# Remote_Control.net
KiCad netlist of a schematic drawn in Altium Designer
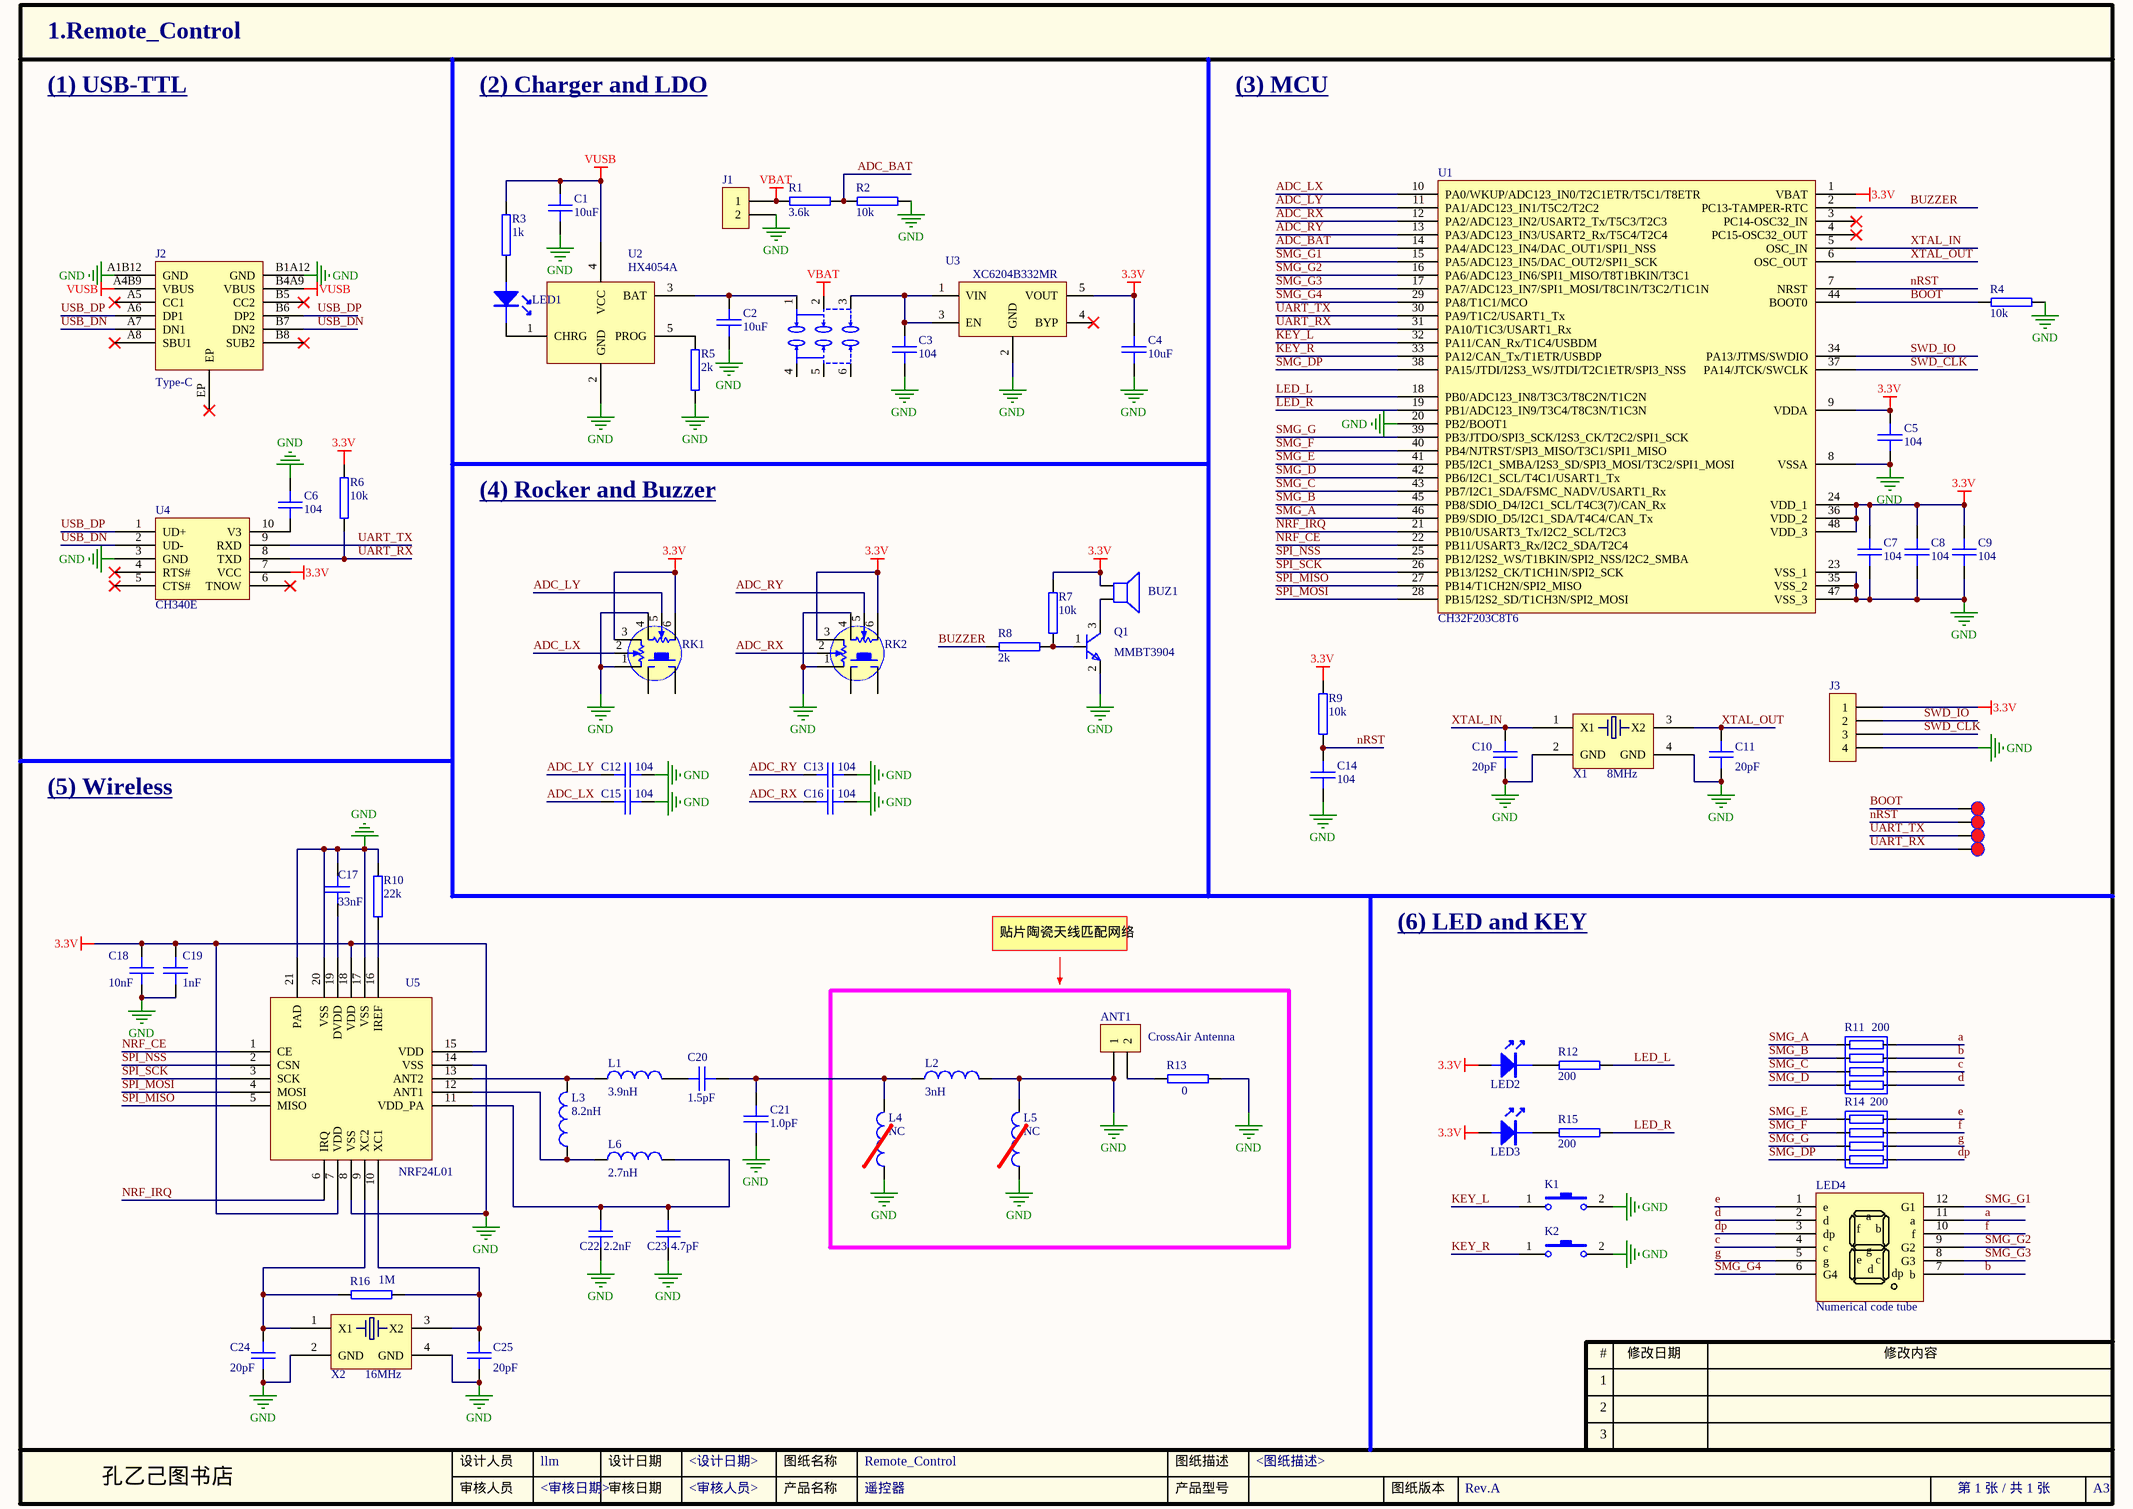
[diagram p0: Remote_Control.SchDoc]

(export (version "E")
  (design (tool "Eeschema 10.0.6"))
  (components
    (comp (ref "ANT1")
      (value "CrossAir Antenna")
      (footprint "ANT-SMD_L3.1-W1.6")
      (description "Connector")
      (libsource (lib "") (part "CON2_1"))
    )
    (comp (ref "BOOT")
      (value "BOOT")
      (footprint "PAD-40")
      (description "测试点")
      (libsource (lib "MY_Schlib") (part "TEST-DOT"))
    )
    (comp (ref "BUZ1")
      (value "BUZZER")
      (footprint "BUZ-TH_BD9.6-P5.00-D0.7-FD")
      (description "蜂鸣器")
      (libsource (lib "Schlib1") (part "BUZZER"))
    )
    (comp (ref "C1")
      (value "10uF")
      (footprint "0805C")
      (description "电容")
      (libsource (lib "MY_Schlib") (part "CAP"))
    )
    (comp (ref "C2")
      (value "10uF")
      (footprint "0805C")
      (description "电容")
      (libsource (lib "MY_Schlib") (part "CAP"))
    )
    (comp (ref "C3")
      (value "104")
      (footprint "0402C")
      (description "电容")
      (libsource (lib "MY_Schlib") (part "CAP"))
    )
    (comp (ref "C4")
      (value "10uF")
      (footprint "0805C")
      (description "电容")
      (libsource (lib "MY_Schlib") (part "CAP"))
    )
    (comp (ref "C5")
      (value "104")
      (footprint "0402C")
      (description "电容")
      (libsource (lib "MY_Schlib") (part "CAP"))
    )
    (comp (ref "C6")
      (value "104")
      (footprint "0402C")
      (description "电容")
      (libsource (lib "MY_Schlib") (part "CAP"))
    )
    (comp (ref "C7")
      (value "104")
      (footprint "0402C")
      (description "电容")
      (libsource (lib "MY_Schlib") (part "CAP"))
    )
    (comp (ref "C8")
      (value "104")
      (footprint "0402C")
      (description "电容")
      (libsource (lib "MY_Schlib") (part "CAP"))
    )
    (comp (ref "C9")
      (value "104")
      (footprint "0402C")
      (description "电容")
      (libsource (lib "MY_Schlib") (part "CAP"))
    )
    (comp (ref "C10")
      (value "20pF")
      (footprint "0402C")
      (description "电容")
      (libsource (lib "MY_Schlib") (part "CAP"))
    )
    (comp (ref "C11")
      (value "20pF")
      (footprint "0402C")
      (description "电容")
      (libsource (lib "MY_Schlib") (part "CAP"))
    )
    (comp (ref "C12")
      (value "104")
      (footprint "0402C")
      (description "电容")
      (libsource (lib "MY_Schlib") (part "CAP"))
    )
    (comp (ref "C13")
      (value "104")
      (footprint "0402C")
      (description "电容")
      (libsource (lib "MY_Schlib") (part "CAP"))
    )
    (comp (ref "C14")
      (value "104")
      (footprint "0402C")
      (description "电容")
      (libsource (lib "MY_Schlib") (part "CAP"))
    )
    (comp (ref "C15")
      (value "104")
      (footprint "0402C")
      (description "电容")
      (libsource (lib "MY_Schlib") (part "CAP"))
    )
    (comp (ref "C16")
      (value "104")
      (footprint "0402C")
      (description "电容")
      (libsource (lib "MY_Schlib") (part "CAP"))
    )
    (comp (ref "C17")
      (value "33nF")
      (footprint "0402C")
      (description "电容")
      (libsource (lib "MY_Schlib") (part "CAP"))
    )
    (comp (ref "C18")
      (value "10nF")
      (footprint "0402C")
      (description "电容")
      (libsource (lib "MY_Schlib") (part "CAP"))
    )
    (comp (ref "C19")
      (value "1nF")
      (footprint "0402C")
      (description "电容")
      (libsource (lib "MY_Schlib") (part "CAP"))
    )
    (comp (ref "C20")
      (value "1.5pF")
      (footprint "0402C")
      (description "电容")
      (libsource (lib "MY_Schlib") (part "CAP"))
    )
    (comp (ref "C21")
      (value "1.0pF")
      (footprint "0402C")
      (description "电容")
      (libsource (lib "MY_Schlib") (part "CAP"))
    )
    (comp (ref "C22")
      (value "2.2nF")
      (footprint "0402C")
      (description "电容")
      (libsource (lib "MY_Schlib") (part "CAP"))
    )
    (comp (ref "C23")
      (value "4.7pF")
      (footprint "0402C")
      (description "电容")
      (libsource (lib "MY_Schlib") (part "CAP"))
    )
    (comp (ref "C24")
      (value "20pF")
      (footprint "0402C")
      (description "电容")
      (libsource (lib "MY_Schlib") (part "CAP"))
    )
    (comp (ref "C25")
      (value "20pF")
      (footprint "0402C")
      (description "电容")
      (libsource (lib "MY_Schlib") (part "CAP"))
    )
    (comp (ref "J1")
      (value "CON2")
      (footprint "SIP-2-2.54")
      (description "Connector")
      (libsource (lib "MY_Schlib") (part "CON2"))
    )
    (comp (ref "J2")
      (value "Type-C")
      (footprint "USB-C-SMD_TYPE-C-16P-1")
      (libsource (lib "MY_Schlib") (part "Type-C"))
    )
    (comp (ref "J3")
      (value "CON4")
      (footprint "SIP-4-2.54")
      (description "Connector")
      (libsource (lib "MY_Schlib") (part "CON4"))
    )
    (comp (ref "K1")
      (value "BUTTON")
      (footprint "KEY-TH_4P-L7.5-W6.8-P4.50-LS7.2")
      (description "按键开关")
      (libsource (lib "MY_Schlib") (part "BUTTON"))
    )
    (comp (ref "K2")
      (value "BUTTON")
      (footprint "KEY-TH_4P-L7.5-W6.8-P4.50-LS7.2")
      (description "按键开关")
      (libsource (lib "MY_Schlib") (part "BUTTON"))
    )
    (comp (ref "L1")
      (value "3.9nH")
      (footprint "0402R")
      (description "电感")
      (libsource (lib "MY_Schlib") (part "INDUCTOR_1"))
    )
    (comp (ref "L2")
      (value "3nH")
      (footprint "0402R")
      (description "电感")
      (libsource (lib "MY_Schlib") (part "INDUCTOR_1"))
    )
    (comp (ref "L3")
      (value "8.2nH")
      (footprint "0402R")
      (description "电感")
      (libsource (lib "") (part "INDUCTOR_1_1"))
    )
    (comp (ref "L4")
      (value "NC")
      (footprint "0402R")
      (description "电感")
      (libsource (lib "") (part "INDUCTOR_1_1"))
    )
    (comp (ref "L5")
      (value "NC")
      (footprint "0402R")
      (description "电感")
      (libsource (lib "") (part "INDUCTOR_1_1"))
    )
    (comp (ref "L6")
      (value "2.7nH")
      (footprint "0402R")
      (description "电感")
      (libsource (lib "MY_Schlib") (part "INDUCTOR_1"))
    )
    (comp (ref "LED1")
      (value "Red")
      (footprint "LED-0603")
      (description "发光二极管")
      (libsource (lib "MY_Schlib") (part "LED"))
    )
    (comp (ref "LED2")
      (value "Blue")
      (footprint "LED-0603")
      (description "发光二极管")
      (libsource (lib "MY_Schlib") (part "LED"))
    )
    (comp (ref "LED3")
      (value "Blue")
      (footprint "LED-0603")
      (description "发光二极管")
      (libsource (lib "MY_Schlib") (part "LED"))
    )
    (comp (ref "LED4")
      (value "Numerical code tube")
      (footprint "0.28寸四位共阴数码管")
      (description "四位共阴数码管")
      (libsource (lib "Schlib1") (part "Numerical code tube"))
    )
    (comp (ref "Q1")
      (value "MMBT3904")
      (footprint "SOT-23")
      (description "NPN三极管")
      (libsource (lib "MY_Schlib") (part "NPN"))
    )
    (comp (ref "R1")
      (value "3.6k")
      (footprint "0402R")
      (description "电阻")
      (libsource (lib "MY_Schlib") (part "RES"))
    )
    (comp (ref "R2")
      (value "10k")
      (footprint "0402R")
      (description "电阻")
      (libsource (lib "MY_Schlib") (part "RES"))
    )
    (comp (ref "R3")
      (value "1k")
      (footprint "0402R")
      (description "电阻")
      (libsource (lib "MY_Schlib") (part "RES"))
    )
    (comp (ref "R4")
      (value "10k")
      (footprint "0402R")
      (description "电阻")
      (libsource (lib "MY_Schlib") (part "RES"))
    )
    (comp (ref "R5")
      (value "2k")
      (footprint "0402R")
      (description "电阻")
      (libsource (lib "MY_Schlib") (part "RES"))
    )
    (comp (ref "R6")
      (value "10k")
      (footprint "0402R")
      (description "电阻")
      (libsource (lib "MY_Schlib") (part "RES"))
    )
    (comp (ref "R7")
      (value "10k")
      (footprint "0402R")
      (description "电阻")
      (libsource (lib "MY_Schlib") (part "RES"))
    )
    (comp (ref "R8")
      (value "2k")
      (footprint "0402R")
      (description "电阻")
      (libsource (lib "MY_Schlib") (part "RES"))
    )
    (comp (ref "R9")
      (value "10k")
      (footprint "0402R")
      (description "电阻")
      (libsource (lib "MY_Schlib") (part "RES"))
    )
    (comp (ref "R10")
      (value "22k")
      (footprint "0402R")
      (description "电阻")
      (libsource (lib "MY_Schlib") (part "RES"))
    )
    (comp (ref "R11")
      (value "200")
      (footprint "RES-0603-8P")
      (description "排阻")
      (libsource (lib "MY_Schlib") (part "RES_4"))
    )
    (comp (ref "R12")
      (value "200")
      (footprint "0402R")
      (description "电阻")
      (libsource (lib "MY_Schlib") (part "RES"))
    )
    (comp (ref "R13")
      (value "0")
      (footprint "0402R")
      (description "电阻")
      (libsource (lib "MY_Schlib") (part "RES"))
    )
    (comp (ref "R14")
      (value "200")
      (footprint "RES-0603-8P")
      (description "排阻")
      (libsource (lib "MY_Schlib") (part "RES_4"))
    )
    (comp (ref "R15")
      (value "200")
      (footprint "0402R")
      (description "电阻")
      (libsource (lib "MY_Schlib") (part "RES"))
    )
    (comp (ref "R16")
      (value "1M")
      (footprint "0402R")
      (description "电阻")
      (libsource (lib "MY_Schlib") (part "RES"))
    )
    (comp (ref "RK1")
      (value "ROCKER")
      (footprint "ROCKER")
      (description "摇杆电位器")
      (libsource (lib "Schlib1") (part "ROCKER"))
    )
    (comp (ref "RK2")
      (value "ROCKER")
      (footprint "ROCKER")
      (description "摇杆电位器")
      (libsource (lib "Schlib1") (part "ROCKER"))
    )
    (comp (ref "RST")
      (value "RST")
      (footprint "PAD-40")
      (description "测试点")
      (libsource (lib "MY_Schlib") (part "TEST-DOT"))
    )
    (comp (ref "Rx")
      (value "Rx")
      (footprint "PAD-40")
      (description "测试点")
      (libsource (lib "MY_Schlib") (part "TEST-DOT"))
    )
    (comp (ref "SW1")
      (value "MST22D18G2")
      (footprint "SW-SMD_MST22D18G2")
      (description "六脚拨动开关")
      (fields (field (name "MANUFACTURER") "SHOU HAN(首韩)"))
      (libsource (lib "Schlib1") (part "MST22D18G2"))
    )
    (comp (ref "Tx")
      (value "Tx")
      (footprint "PAD-40")
      (description "测试点")
      (libsource (lib "MY_Schlib") (part "TEST-DOT"))
    )
    (comp (ref "U1")
      (value "CH32F203C8T6")
      (footprint "LQFP-48_7x7")
      (description "STM32单片机48引脚")
      (libsource (lib "MY_Schlib") (part "STM32F103C"))
    )
    (comp (ref "U2")
      (value "HX4054A")
      (footprint "SOT-23-5_L3.0-W1.7-P0.95-LS2.8-BR")
      (description "锂电池充电芯片")
      (libsource (lib "Schlib1") (part "HX4054A"))
    )
    (comp (ref "U3")
      (value "XC6204B332MR")
      (footprint "SOT-23-5")
      (description "LDO, 3.0V输出")
      (libsource (lib "MY_Schlib") (part "ZL6205A30TS5"))
    )
    (comp (ref "U4")
      (value "CH340E")
      (footprint "MSOP-10_L3.0-W3.0-P0.50-LS5.0-BL")
      (description "USB-TTL芯片")
      (libsource (lib "MY_Schlib") (part "CH340E"))
    )
    (comp (ref "U5")
      (value "NRF24L01")
      (footprint "QFN-20_L4.0-W4.0-P0.50-BL-EP")
      (description "2.4G无线通信芯片")
      (libsource (lib "MY_Schlib") (part "NRF24L01"))
    )
    (comp (ref "X1")
      (value "8MHz")
      (footprint "OSCCC250X320X80-4N")
      (description "4pin贴片无源晶振")
      (libsource (lib "MY_Schlib") (part "XTAL4"))
    )
    (comp (ref "X2")
      (value "16MHz")
      (footprint "OSCCC250X320X80-4N")
      (description "4pin贴片无源晶振")
      (libsource (lib "MY_Schlib") (part "XTAL4"))
    )
  )
  (nets
    (net (code "1") (name "/ADC_BAT") (class "Default")
      (node (ref "R1") (pin "1") (pinfunction "1_1") (pintype "passive"))
      (node (ref "R2") (pin "2") (pinfunction "2_2") (pintype "passive"))
      (node (ref "U1") (pin "14") (pinfunction "PA4/ADC123_IN4/DAC_OUT1/SPI1_NSS_14") (pintype "passive"))
    )
    (net (code "2") (name "/ADC_LX") (class "Default")
      (node (ref "C15") (pin "2") (pinfunction "2_2") (pintype "passive"))
      (node (ref "RK1") (pin "2") (pinfunction "2_2") (pintype "passive"))
      (node (ref "U1") (pin "10") (pinfunction "PA0/WKUP/ADC123_IN0/T2C1ETR/T5C1/T8ETR_10") (pintype "passive"))
    )
    (net (code "3") (name "/ADC_LY") (class "Default")
      (node (ref "C12") (pin "2") (pinfunction "2_2") (pintype "passive"))
      (node (ref "RK1") (pin "5") (pinfunction "5_5") (pintype "passive"))
      (node (ref "U1") (pin "11") (pinfunction "PA1/ADC123_IN1/T5C2/T2C2_11") (pintype "passive"))
    )
    (net (code "4") (name "/ADC_RX") (class "Default")
      (node (ref "C16") (pin "2") (pinfunction "2_2") (pintype "passive"))
      (node (ref "RK2") (pin "2") (pinfunction "2_2") (pintype "passive"))
      (node (ref "U1") (pin "12") (pinfunction "PA2/ADC123_IN2/USART2_Tx/T5C3/T2C3_12") (pintype "passive"))
    )
    (net (code "5") (name "/ADC_RY") (class "Default")
      (node (ref "C13") (pin "2") (pinfunction "2_2") (pintype "passive"))
      (node (ref "RK2") (pin "5") (pinfunction "5_5") (pintype "passive"))
      (node (ref "U1") (pin "13") (pinfunction "PA3/ADC123_IN3/USART2_Rx/T5C4/T2C4_13") (pintype "passive"))
    )
    (net (code "6") (name "/BOOT") (class "Default")
      (node (ref "BOOT") (pin "1") (pinfunction "1_1") (pintype "passive"))
      (node (ref "R4") (pin "1") (pinfunction "1_1") (pintype "passive"))
      (node (ref "U1") (pin "44") (pinfunction "BOOT0_44") (pintype "passive"))
    )
    (net (code "7") (name "/BUZZER") (class "Default")
      (node (ref "R8") (pin "2") (pinfunction "2_2") (pintype "passive"))
      (node (ref "U1") (pin "2") (pinfunction "PC13-TAMPER-RTC_2") (pintype "passive"))
    )
    (net (code "8") (name "/KEY_L") (class "Default")
      (node (ref "K1") (pin "1") (pinfunction "1_1") (pintype "passive"))
      (node (ref "U1") (pin "32") (pinfunction "PA11/CAN_Rx/T1C4/USBDM_32") (pintype "passive"))
    )
    (net (code "9") (name "/KEY_R") (class "Default")
      (node (ref "K2") (pin "1") (pinfunction "1_1") (pintype "passive"))
      (node (ref "U1") (pin "33") (pinfunction "PA12/CAN_Tx/T1ETR/USBDP_33") (pintype "passive"))
    )
    (net (code "10") (name "/LED_L") (class "Default")
      (node (ref "R12") (pin "1") (pinfunction "1_1") (pintype "passive"))
      (node (ref "U1") (pin "18") (pinfunction "PB0/ADC123_IN8/T3C3/T8C2N/T1C2N_18") (pintype "passive"))
    )
    (net (code "11") (name "/LED_R") (class "Default")
      (node (ref "R15") (pin "1") (pinfunction "1_1") (pintype "passive"))
      (node (ref "U1") (pin "19") (pinfunction "PB1/ADC123_IN9/T3C4/T8C3N/T1C3N_19") (pintype "passive"))
    )
    (net (code "12") (name "/NRF_CE") (class "Default")
      (node (ref "U1") (pin "22") (pinfunction "PB11/USART3_Rx/I2C2_SDA/T2C4_22") (pintype "passive"))
      (node (ref "U5") (pin "1") (pinfunction "CE_1") (pintype "passive"))
    )
    (net (code "13") (name "/NRF_IRQ") (class "Default")
      (node (ref "U1") (pin "21") (pinfunction "PB10/USART3_Tx/I2C2_SCL/T2C3_21") (pintype "passive"))
      (node (ref "U5") (pin "6") (pinfunction "IRQ_6") (pintype "passive"))
    )
    (net (code "14") (name "/SMG_A") (class "Default")
      (node (ref "R11") (pin "5") (pinfunction "5_5") (pintype "passive"))
      (node (ref "U1") (pin "46") (pinfunction "PB9/SDIO_D5/I2C1_SDA/T4C4/CAN_Tx_46") (pintype "passive"))
    )
    (net (code "15") (name "/SMG_B") (class "Default")
      (node (ref "R11") (pin "6") (pinfunction "6_6") (pintype "passive"))
      (node (ref "U1") (pin "45") (pinfunction "PB8/SDIO_D4/I2C1_SCL/T4C3(7)/CAN_Rx_45") (pintype "passive"))
    )
    (net (code "16") (name "/SMG_C") (class "Default")
      (node (ref "R11") (pin "7") (pinfunction "7_7") (pintype "passive"))
      (node (ref "U1") (pin "43") (pinfunction "PB7/I2C1_SDA/FSMC_NADV/USART1_Rx_43") (pintype "passive"))
    )
    (net (code "17") (name "/SMG_D") (class "Default")
      (node (ref "R11") (pin "8") (pinfunction "8_8") (pintype "passive"))
      (node (ref "U1") (pin "42") (pinfunction "PB6/I2C1_SCL/T4C1/USART1_Tx_42") (pintype "passive"))
    )
    (net (code "18") (name "/SMG_DP") (class "Default")
      (node (ref "R14") (pin "8") (pinfunction "8_8") (pintype "passive"))
      (node (ref "U1") (pin "38") (pinfunction "PA15/JTDI/I2S3_WS/JTDI/T2C1ETR/SPI3_NSS_38") (pintype "passive"))
    )
    (net (code "19") (name "/SMG_E") (class "Default")
      (node (ref "R14") (pin "5") (pinfunction "5_5") (pintype "passive"))
      (node (ref "U1") (pin "41") (pinfunction "PB5/I2C1_SMBA/I2S3_SD/SPI3_MOSI/T3C2/SPI1_MOSI_41") (pintype "passive"))
    )
    (net (code "20") (name "/SMG_F") (class "Default")
      (node (ref "R14") (pin "6") (pinfunction "6_6") (pintype "passive"))
      (node (ref "U1") (pin "40") (pinfunction "PB4/NJTRST/SPI3_MISO/T3C1/SPI1_MISO_40") (pintype "passive"))
    )
    (net (code "21") (name "/SMG_G") (class "Default")
      (node (ref "R14") (pin "7") (pinfunction "7_7") (pintype "passive"))
      (node (ref "U1") (pin "39") (pinfunction "PB3/JTDO/SPI3_SCK/I2S3_CK/T2C2/SPI1_SCK_39") (pintype "passive"))
    )
    (net (code "22") (name "/SMG_G1") (class "Default")
      (node (ref "LED4") (pin "12") (pinfunction "G1_12") (pintype "passive"))
      (node (ref "U1") (pin "15") (pinfunction "PA5/ADC123_IN5/DAC_OUT2/SPI1_SCK_15") (pintype "passive"))
    )
    (net (code "23") (name "/SMG_G2") (class "Default")
      (node (ref "LED4") (pin "9") (pinfunction "G2_9") (pintype "passive"))
      (node (ref "U1") (pin "16") (pinfunction "PA6/ADC123_IN6/SPI1_MISO/T8T1BKIN/T3C1_16") (pintype "passive"))
    )
    (net (code "24") (name "/SMG_G3") (class "Default")
      (node (ref "LED4") (pin "8") (pinfunction "G3_8") (pintype "passive"))
      (node (ref "U1") (pin "17") (pinfunction "PA7/ADC123_IN7/SPI1_MOSI/T8C1N/T3C2/T1C1N_17") (pintype "passive"))
    )
    (net (code "25") (name "/SMG_G4") (class "Default")
      (node (ref "LED4") (pin "6") (pinfunction "G4_6") (pintype "passive"))
      (node (ref "U1") (pin "29") (pinfunction "PA8/T1C1/MCO_29") (pintype "passive"))
    )
    (net (code "26") (name "/SPI_MISO") (class "Default")
      (node (ref "U1") (pin "27") (pinfunction "PB14/T1CH2N/SPI2_MISO_27") (pintype "passive"))
      (node (ref "U5") (pin "5") (pinfunction "MISO_5") (pintype "passive"))
    )
    (net (code "27") (name "/SPI_MOSI") (class "Default")
      (node (ref "U1") (pin "28") (pinfunction "PB15/I2S2_SD/T1CH3N/SPI2_MOSI_28") (pintype "passive"))
      (node (ref "U5") (pin "4") (pinfunction "MOSI_4") (pintype "passive"))
    )
    (net (code "28") (name "/SPI_NSS") (class "Default")
      (node (ref "U1") (pin "25") (pinfunction "PB12/I2S2_WS/T1BKIN/SPI2_NSS/I2C2_SMBA_25") (pintype "passive"))
      (node (ref "U5") (pin "2") (pinfunction "CSN_2") (pintype "passive"))
    )
    (net (code "29") (name "/SPI_SCK") (class "Default")
      (node (ref "U1") (pin "26") (pinfunction "PB13/I2S2_CK/T1CH1N/SPI2_SCK_26") (pintype "passive"))
      (node (ref "U5") (pin "3") (pinfunction "SCK_3") (pintype "passive"))
    )
    (net (code "30") (name "/SWD_CLK") (class "Default")
      (node (ref "J3") (pin "3") (pinfunction "3_3") (pintype "passive"))
      (node (ref "U1") (pin "37") (pinfunction "PA14/JTCK/SWCLK_37") (pintype "passive"))
    )
    (net (code "31") (name "/SWD_IO") (class "Default")
      (node (ref "J3") (pin "2") (pinfunction "2_2") (pintype "passive"))
      (node (ref "U1") (pin "34") (pinfunction "PA13/JTMS/SWDIO_34") (pintype "passive"))
    )
    (net (code "32") (name "/UART_RX") (class "Default")
      (node (ref "R6") (pin "1") (pinfunction "1_1") (pintype "passive"))
      (node (ref "Rx") (pin "1") (pinfunction "1_1") (pintype "passive"))
      (node (ref "U1") (pin "31") (pinfunction "PA10/T1C3/USART1_Rx_31") (pintype "passive"))
      (node (ref "U4") (pin "8") (pinfunction "TXD_8") (pintype "passive"))
    )
    (net (code "33") (name "/UART_TX") (class "Default")
      (node (ref "Tx") (pin "1") (pinfunction "1_1") (pintype "passive"))
      (node (ref "U1") (pin "30") (pinfunction "PA9/T1C2/USART1_Tx_30") (pintype "passive"))
      (node (ref "U4") (pin "9") (pinfunction "RXD_9") (pintype "passive"))
    )
    (net (code "34") (name "/USB_DN") (class "Default")
      (node (ref "J2") (pin "A7") (pinfunction "DN1_A7") (pintype "passive"))
      (node (ref "J2") (pin "B7") (pinfunction "DN2_B7") (pintype "passive"))
      (node (ref "U4") (pin "2") (pinfunction "UD-_2") (pintype "passive"))
    )
    (net (code "35") (name "/USB_DP") (class "Default")
      (node (ref "J2") (pin "A6") (pinfunction "DP1_A6") (pintype "passive"))
      (node (ref "J2") (pin "B6") (pinfunction "DP2_B6") (pintype "passive"))
      (node (ref "U4") (pin "1") (pinfunction "UD+_1") (pintype "passive"))
    )
    (net (code "36") (name "/XTAL_IN") (class "Default")
      (node (ref "C10") (pin "2") (pinfunction "2_2") (pintype "passive"))
      (node (ref "U1") (pin "5") (pinfunction "OSC_IN_5") (pintype "passive"))
      (node (ref "X1") (pin "1") (pinfunction "X1_1") (pintype "passive"))
    )
    (net (code "37") (name "/XTAL_OUT") (class "Default")
      (node (ref "C11") (pin "2") (pinfunction "2_2") (pintype "passive"))
      (node (ref "U1") (pin "6") (pinfunction "OSC_OUT_6") (pintype "passive"))
      (node (ref "X1") (pin "3") (pinfunction "X2_3") (pintype "passive"))
    )
    (net (code "38") (name "/a") (class "Default")
      (node (ref "LED4") (pin "11") (pinfunction "a_11") (pintype "passive"))
      (node (ref "R11") (pin "4") (pinfunction "4_4") (pintype "passive"))
    )
    (net (code "39") (name "/b") (class "Default")
      (node (ref "LED4") (pin "7") (pinfunction "b_7") (pintype "passive"))
      (node (ref "R11") (pin "3") (pinfunction "3_3") (pintype "passive"))
    )
    (net (code "40") (name "/c") (class "Default")
      (node (ref "LED4") (pin "4") (pinfunction "c_4") (pintype "passive"))
      (node (ref "R11") (pin "2") (pinfunction "2_2") (pintype "passive"))
    )
    (net (code "41") (name "/d") (class "Default")
      (node (ref "LED4") (pin "2") (pinfunction "d_2") (pintype "passive"))
      (node (ref "R11") (pin "1") (pinfunction "1_1") (pintype "passive"))
    )
    (net (code "42") (name "/dp") (class "Default")
      (node (ref "LED4") (pin "3") (pinfunction "dp_3") (pintype "passive"))
      (node (ref "R14") (pin "1") (pinfunction "1_1") (pintype "passive"))
    )
    (net (code "43") (name "/e") (class "Default")
      (node (ref "LED4") (pin "1") (pinfunction "e_1") (pintype "passive"))
      (node (ref "R14") (pin "4") (pinfunction "4_4") (pintype "passive"))
    )
    (net (code "44") (name "/f") (class "Default")
      (node (ref "LED4") (pin "10") (pinfunction "f_10") (pintype "passive"))
      (node (ref "R14") (pin "3") (pinfunction "3_3") (pintype "passive"))
    )
    (net (code "45") (name "/g") (class "Default")
      (node (ref "LED4") (pin "5") (pinfunction "g_5") (pintype "passive"))
      (node (ref "R14") (pin "2") (pinfunction "2_2") (pintype "passive"))
    )
    (net (code "46") (name "/nRST") (class "Default")
      (node (ref "C14") (pin "2") (pinfunction "2_2") (pintype "passive"))
      (node (ref "R9") (pin "1") (pinfunction "1_1") (pintype "passive"))
      (node (ref "RST") (pin "1") (pinfunction "1_1") (pintype "passive"))
      (node (ref "U1") (pin "7") (pinfunction "NRST_7") (pintype "passive"))
    )
    (net (code "47") (name "3.3V") (class "Default")
      (node (ref "BUZ1") (pin "1") (pinfunction "+_1") (pintype "passive"))
      (node (ref "C18") (pin "1") (pinfunction "1_1") (pintype "passive"))
      (node (ref "C19") (pin "1") (pinfunction "1_1") (pintype "passive"))
      (node (ref "C4") (pin "1") (pinfunction "1_1") (pintype "passive"))
      (node (ref "C5") (pin "2") (pinfunction "2_2") (pintype "passive"))
      (node (ref "C7") (pin "2") (pinfunction "2_2") (pintype "passive"))
      (node (ref "C8") (pin "2") (pinfunction "2_2") (pintype "passive"))
      (node (ref "C9") (pin "2") (pinfunction "2_2") (pintype "passive"))
      (node (ref "J3") (pin "1") (pinfunction "1_1") (pintype "passive"))
      (node (ref "LED2") (pin "1") (pinfunction "1_1") (pintype "passive"))
      (node (ref "LED3") (pin "1") (pinfunction "1_1") (pintype "passive"))
      (node (ref "R6") (pin "2") (pinfunction "2_2") (pintype "passive"))
      (node (ref "R7") (pin "2") (pinfunction "2_2") (pintype "passive"))
      (node (ref "R9") (pin "2") (pinfunction "2_2") (pintype "passive"))
      (node (ref "RK1") (pin "3") (pinfunction "3_3") (pintype "passive"))
      (node (ref "RK1") (pin "6") (pinfunction "6_6") (pintype "passive"))
      (node (ref "RK2") (pin "3") (pinfunction "3_3") (pintype "passive"))
      (node (ref "RK2") (pin "6") (pinfunction "6_6") (pintype "passive"))
      (node (ref "U1") (pin "1") (pinfunction "VBAT_1") (pintype "passive"))
      (node (ref "U1") (pin "24") (pinfunction "VDD_1_24") (pintype "passive"))
      (node (ref "U1") (pin "36") (pinfunction "VDD_2_36") (pintype "passive"))
      (node (ref "U1") (pin "48") (pinfunction "VDD_3_48") (pintype "passive"))
      (node (ref "U1") (pin "9") (pinfunction "VDDA_9") (pintype "passive"))
      (node (ref "U3") (pin "5") (pinfunction "VOUT_5") (pintype "passive"))
      (node (ref "U4") (pin "7") (pinfunction "VCC_7") (pintype "passive"))
      (node (ref "U5") (pin "15") (pinfunction "VDD_15") (pintype "passive"))
      (node (ref "U5") (pin "18") (pinfunction "VDD_18") (pintype "passive"))
      (node (ref "U5") (pin "7") (pinfunction "VDD_7") (pintype "passive"))
    )
    (net (code "48") (name "GND") (class "Default")
      (node (ref "ANT1") (pin "1") (pinfunction "1_1") (pintype "passive"))
      (node (ref "C1") (pin "2") (pinfunction "2_2") (pintype "passive"))
      (node (ref "C10") (pin "1") (pinfunction "1_1") (pintype "passive"))
      (node (ref "C11") (pin "1") (pinfunction "1_1") (pintype "passive"))
      (node (ref "C12") (pin "1") (pinfunction "1_1") (pintype "passive"))
      (node (ref "C13") (pin "1") (pinfunction "1_1") (pintype "passive"))
      (node (ref "C14") (pin "1") (pinfunction "1_1") (pintype "passive"))
      (node (ref "C15") (pin "1") (pinfunction "1_1") (pintype "passive"))
      (node (ref "C16") (pin "1") (pinfunction "1_1") (pintype "passive"))
      (node (ref "C17") (pin "1") (pinfunction "1_1") (pintype "passive"))
      (node (ref "C18") (pin "2") (pinfunction "2_2") (pintype "passive"))
      (node (ref "C19") (pin "2") (pinfunction "2_2") (pintype "passive"))
      (node (ref "C2") (pin "2") (pinfunction "2_2") (pintype "passive"))
      (node (ref "C21") (pin "1") (pinfunction "1_1") (pintype "passive"))
      (node (ref "C22") (pin "2") (pinfunction "2_2") (pintype "passive"))
      (node (ref "C23") (pin "2") (pinfunction "2_2") (pintype "passive"))
      (node (ref "C24") (pin "1") (pinfunction "1_1") (pintype "passive"))
      (node (ref "C25") (pin "1") (pinfunction "1_1") (pintype "passive"))
      (node (ref "C3") (pin "2") (pinfunction "2_2") (pintype "passive"))
      (node (ref "C4") (pin "2") (pinfunction "2_2") (pintype "passive"))
      (node (ref "C5") (pin "1") (pinfunction "1_1") (pintype "passive"))
      (node (ref "C6") (pin "2") (pinfunction "2_2") (pintype "passive"))
      (node (ref "C7") (pin "1") (pinfunction "1_1") (pintype "passive"))
      (node (ref "C8") (pin "1") (pinfunction "1_1") (pintype "passive"))
      (node (ref "C9") (pin "1") (pinfunction "1_1") (pintype "passive"))
      (node (ref "J1") (pin "2") (pinfunction "2_2") (pintype "passive"))
      (node (ref "J2") (pin "A1B12") (pinfunction "GND_A1B12") (pintype "passive"))
      (node (ref "J2") (pin "B1A12") (pinfunction "GND_B1A12") (pintype "passive"))
      (node (ref "J3") (pin "4") (pinfunction "4_4") (pintype "passive"))
      (node (ref "K1") (pin "2") (pinfunction "2_2") (pintype "passive"))
      (node (ref "K2") (pin "2") (pinfunction "2_2") (pintype "passive"))
      (node (ref "L2") (pin "2") (pinfunction "2_2") (pintype "passive"))
      (node (ref "L4") (pin "1") (pinfunction "1_1") (pintype "passive"))
      (node (ref "L5") (pin "1") (pinfunction "1_1") (pintype "passive"))
      (node (ref "L5") (pin "2") (pinfunction "2_2") (pintype "passive"))
      (node (ref "Q1") (pin "2") (pinfunction "E_2") (pintype "passive"))
      (node (ref "R10") (pin "1") (pinfunction "1_1") (pintype "passive"))
      (node (ref "R13") (pin "2") (pinfunction "2_2") (pintype "passive"))
      (node (ref "R2") (pin "1") (pinfunction "1_1") (pintype "passive"))
      (node (ref "R4") (pin "2") (pinfunction "2_2") (pintype "passive"))
      (node (ref "R5") (pin "1") (pinfunction "1_1") (pintype "passive"))
      (node (ref "RK1") (pin "1") (pinfunction "1_1") (pintype "passive"))
      (node (ref "RK1") (pin "4") (pinfunction "4_4") (pintype "passive"))
      (node (ref "RK2") (pin "1") (pinfunction "1_1") (pintype "passive"))
      (node (ref "RK2") (pin "4") (pinfunction "4_4") (pintype "passive"))
      (node (ref "U1") (pin "20") (pinfunction "PB2/BOOT1_20") (pintype "passive"))
      (node (ref "U1") (pin "23") (pinfunction "VSS_1_23") (pintype "passive"))
      (node (ref "U1") (pin "35") (pinfunction "VSS_2_35") (pintype "passive"))
      (node (ref "U1") (pin "47") (pinfunction "VSS_3_47") (pintype "passive"))
      (node (ref "U1") (pin "8") (pinfunction "VSSA_8") (pintype "passive"))
      (node (ref "U2") (pin "2") (pinfunction "GND_2") (pintype "passive"))
      (node (ref "U3") (pin "2") (pinfunction "GND_2") (pintype "passive"))
      (node (ref "U4") (pin "3") (pinfunction "GND_3") (pintype "passive"))
      (node (ref "U5") (pin "14") (pinfunction "VSS_14") (pintype "passive"))
      (node (ref "U5") (pin "17") (pinfunction "VSS_17") (pintype "passive"))
      (node (ref "U5") (pin "20") (pinfunction "VSS_20") (pintype "passive"))
      (node (ref "U5") (pin "21") (pinfunction "PAD_21") (pintype "passive"))
      (node (ref "U5") (pin "8") (pinfunction "VSS_8") (pintype "passive"))
      (node (ref "X1") (pin "2") (pinfunction "GND_2") (pintype "passive"))
      (node (ref "X1") (pin "4") (pinfunction "GND_4") (pintype "passive"))
      (node (ref "X2") (pin "2") (pinfunction "GND_2") (pintype "passive"))
      (node (ref "X2") (pin "4") (pinfunction "GND_4") (pintype "passive"))
    )
    (net (code "49") (name "Net-(ANT1-Pad2)") (class "Default")
      (node (ref "ANT1") (pin "2") (pinfunction "2_2") (pintype "passive"))
      (node (ref "R13") (pin "1") (pinfunction "1_1") (pintype "passive"))
    )
    (net (code "50") (name "Net-(BUZ1--)") (class "Default")
      (node (ref "BUZ1") (pin "2") (pinfunction "-_2") (pintype "passive"))
      (node (ref "Q1") (pin "3") (pinfunction "C_3") (pintype "passive"))
    )
    (net (code "51") (name "Net-(C20-Pad1)") (class "Default")
      (node (ref "C20") (pin "1") (pinfunction "1_1") (pintype "passive"))
      (node (ref "L1") (pin "2") (pinfunction "2_2") (pintype "passive"))
    )
    (net (code "52") (name "Net-(C20-Pad2)") (class "Default")
      (node (ref "C20") (pin "2") (pinfunction "2_2") (pintype "passive"))
      (node (ref "C21") (pin "2") (pinfunction "2_2") (pintype "passive"))
      (node (ref "L2") (pin "1") (pinfunction "1_1") (pintype "passive"))
      (node (ref "L4") (pin "2") (pinfunction "2_2") (pintype "passive"))
    )
    (net (code "53") (name "Net-(LED1-Pad1)") (class "Default")
      (node (ref "LED1") (pin "1") (pinfunction "1_1") (pintype "passive"))
      (node (ref "R3") (pin "1") (pinfunction "1_1") (pintype "passive"))
    )
    (net (code "54") (name "Net-(LED2-Pad2)") (class "Default")
      (node (ref "LED2") (pin "2") (pinfunction "2_2") (pintype "passive"))
      (node (ref "R12") (pin "2") (pinfunction "2_2") (pintype "passive"))
    )
    (net (code "55") (name "Net-(LED3-Pad2)") (class "Default")
      (node (ref "LED3") (pin "2") (pinfunction "2_2") (pintype "passive"))
      (node (ref "R15") (pin "2") (pinfunction "2_2") (pintype "passive"))
    )
    (net (code "56") (name "Net-(Q1-B)") (class "Default")
      (node (ref "Q1") (pin "1") (pinfunction "B_1") (pintype "passive"))
      (node (ref "R7") (pin "1") (pinfunction "1_1") (pintype "passive"))
      (node (ref "R8") (pin "1") (pinfunction "1_1") (pintype "passive"))
    )
    (net (code "57") (name "Net-(U2-BAT)") (class "Default")
      (node (ref "C2") (pin "1") (pinfunction "1_1") (pintype "passive"))
      (node (ref "SW1") (pin "1") (pinfunction "1_1") (pintype "passive"))
      (node (ref "U2") (pin "3") (pinfunction "BAT_3") (pintype "passive"))
    )
    (net (code "58") (name "Net-(U2-CHRG)") (class "Default")
      (node (ref "LED1") (pin "2") (pinfunction "2_2") (pintype "passive"))
      (node (ref "U2") (pin "1") (pinfunction "CHRG_1") (pintype "passive"))
    )
    (net (code "59") (name "Net-(U2-PROG)") (class "Default")
      (node (ref "R5") (pin "2") (pinfunction "2_2") (pintype "passive"))
      (node (ref "U2") (pin "5") (pinfunction "PROG_5") (pintype "passive"))
    )
    (net (code "60") (name "Net-(U3-EN)") (class "Default")
      (node (ref "C3") (pin "1") (pinfunction "1_1") (pintype "passive"))
      (node (ref "SW1") (pin "3") (pinfunction "3_3") (pintype "passive"))
      (node (ref "U3") (pin "1") (pinfunction "VIN_1") (pintype "passive"))
      (node (ref "U3") (pin "3") (pinfunction "EN_3") (pintype "passive"))
    )
    (net (code "61") (name "Net-(U4-V3)") (class "Default")
      (node (ref "C6") (pin "1") (pinfunction "1_1") (pintype "passive"))
      (node (ref "U4") (pin "10") (pinfunction "V3_10") (pintype "passive"))
    )
    (net (code "62") (name "Net-(U5-ANT1)") (class "Default")
      (node (ref "L3") (pin "1") (pinfunction "1_1") (pintype "passive"))
      (node (ref "L6") (pin "1") (pinfunction "1_1") (pintype "passive"))
      (node (ref "U5") (pin "12") (pinfunction "ANT1_12") (pintype "passive"))
    )
    (net (code "63") (name "Net-(U5-ANT2)") (class "Default")
      (node (ref "L1") (pin "1") (pinfunction "1_1") (pintype "passive"))
      (node (ref "L3") (pin "2") (pinfunction "2_2") (pintype "passive"))
      (node (ref "U5") (pin "13") (pinfunction "ANT2_13") (pintype "passive"))
    )
    (net (code "64") (name "Net-(U5-DVDD)") (class "Default")
      (node (ref "C17") (pin "2") (pinfunction "2_2") (pintype "passive"))
      (node (ref "U5") (pin "19") (pinfunction "DVDD_19") (pintype "passive"))
    )
    (net (code "65") (name "Net-(U5-IREF)") (class "Default")
      (node (ref "R10") (pin "2") (pinfunction "2_2") (pintype "passive"))
      (node (ref "U5") (pin "16") (pinfunction "IREF_16") (pintype "passive"))
    )
    (net (code "66") (name "Net-(U5-VDD_PA)") (class "Default")
      (node (ref "C22") (pin "1") (pinfunction "1_1") (pintype "passive"))
      (node (ref "C23") (pin "1") (pinfunction "1_1") (pintype "passive"))
      (node (ref "L6") (pin "2") (pinfunction "2_2") (pintype "passive"))
      (node (ref "U5") (pin "11") (pinfunction "VDD_PA_11") (pintype "passive"))
    )
    (net (code "67") (name "Net-(U5-XC1)") (class "Default")
      (node (ref "C25") (pin "2") (pinfunction "2_2") (pintype "passive"))
      (node (ref "R16") (pin "2") (pinfunction "2_2") (pintype "passive"))
      (node (ref "U5") (pin "10") (pinfunction "XC1_10") (pintype "passive"))
      (node (ref "X2") (pin "3") (pinfunction "X2_3") (pintype "passive"))
    )
    (net (code "68") (name "Net-(U5-XC2)") (class "Default")
      (node (ref "C24") (pin "2") (pinfunction "2_2") (pintype "passive"))
      (node (ref "R16") (pin "1") (pinfunction "1_1") (pintype "passive"))
      (node (ref "U5") (pin "9") (pinfunction "XC2_9") (pintype "passive"))
      (node (ref "X2") (pin "1") (pinfunction "X1_1") (pintype "passive"))
    )
    (net (code "69") (name "VBAT") (class "Default")
      (node (ref "J1") (pin "1") (pinfunction "1_1") (pintype "passive"))
      (node (ref "R1") (pin "2") (pinfunction "2_2") (pintype "passive"))
      (node (ref "SW1") (pin "2") (pinfunction "2_2") (pintype "passive"))
    )
    (net (code "70") (name "VUSB") (class "Default")
      (node (ref "C1") (pin "1") (pinfunction "1_1") (pintype "passive"))
      (node (ref "J2") (pin "A4B9") (pinfunction "VBUS_A4B9") (pintype "passive"))
      (node (ref "J2") (pin "B4A9") (pinfunction "VBUS_B4A9") (pintype "passive"))
      (node (ref "R3") (pin "2") (pinfunction "2_2") (pintype "passive"))
      (node (ref "U2") (pin "4") (pinfunction "VCC_4") (pintype "passive"))
    )
    (net (code "71") (name "unconnected-(J2-CC1-PadA5)") (class "Default")
      (node (ref "J2") (pin "A5") (pinfunction "CC1_A5") (pintype "passive+no_connect"))
    )
    (net (code "72") (name "unconnected-(J2-CC2-PadB5)") (class "Default")
      (node (ref "J2") (pin "B5") (pinfunction "CC2_B5") (pintype "passive+no_connect"))
    )
    (net (code "73") (name "unconnected-(J2-PadEP)") (class "Default")
      (node (ref "J2") (pin "EP") (pinfunction "EP_EP") (pintype "passive+no_connect"))
    )
    (net (code "74") (name "unconnected-(J2-SBU1-PadA8)") (class "Default")
      (node (ref "J2") (pin "A8") (pinfunction "SBU1_A8") (pintype "passive+no_connect"))
    )
    (net (code "75") (name "unconnected-(J2-SUB2-PadB8)") (class "Default")
      (node (ref "J2") (pin "B8") (pinfunction "SUB2_B8") (pintype "passive+no_connect"))
    )
    (net (code "76") (name "unconnected-(RK1-PadJ1)") (class "Default")
      (node (ref "RK1") (pin "J1") (pinfunction "J1_J1") (pintype "passive"))
    )
    (net (code "77") (name "unconnected-(RK1-PadJ2)") (class "Default")
      (node (ref "RK1") (pin "J2") (pinfunction "J2_J2") (pintype "passive"))
    )
    (net (code "78") (name "unconnected-(RK2-PadJ1)") (class "Default")
      (node (ref "RK2") (pin "J1") (pinfunction "J1_J1") (pintype "passive"))
    )
    (net (code "79") (name "unconnected-(RK2-PadJ2)") (class "Default")
      (node (ref "RK2") (pin "J2") (pinfunction "J2_J2") (pintype "passive"))
    )
    (net (code "80") (name "unconnected-(SW1-Pad4)") (class "Default")
      (node (ref "SW1") (pin "4") (pinfunction "4_4") (pintype "passive"))
    )
    (net (code "81") (name "unconnected-(SW1-Pad5)") (class "Default")
      (node (ref "SW1") (pin "5") (pinfunction "5_5") (pintype "passive"))
    )
    (net (code "82") (name "unconnected-(SW1-Pad6)") (class "Default")
      (node (ref "SW1") (pin "6") (pinfunction "6_6") (pintype "passive"))
    )
    (net (code "83") (name "unconnected-(U1-PC14-OSC32_IN-Pad3)") (class "Default")
      (node (ref "U1") (pin "3") (pinfunction "PC14-OSC32_IN_3") (pintype "passive+no_connect"))
    )
    (net (code "84") (name "unconnected-(U1-PC15-OSC32_OUT-Pad4)") (class "Default")
      (node (ref "U1") (pin "4") (pinfunction "PC15-OSC32_OUT_4") (pintype "passive+no_connect"))
    )
    (net (code "85") (name "unconnected-(U3-BYP-Pad4)") (class "Default")
      (node (ref "U3") (pin "4") (pinfunction "BYP_4") (pintype "passive+no_connect"))
    )
    (net (code "86") (name "unconnected-(U4-CTS#-Pad5)") (class "Default")
      (node (ref "U4") (pin "5") (pinfunction "CTS#_5") (pintype "passive+no_connect"))
    )
    (net (code "87") (name "unconnected-(U4-RTS#-Pad4)") (class "Default")
      (node (ref "U4") (pin "4") (pinfunction "RTS#_4") (pintype "passive+no_connect"))
    )
    (net (code "88") (name "unconnected-(U4-TNOW-Pad6)") (class "Default")
      (node (ref "U4") (pin "6") (pinfunction "TNOW_6") (pintype "passive+no_connect"))
    )
  )
)
